# EIB_RHD32_HW01.net
KiCad netlist of a schematic drawn in EAGLE
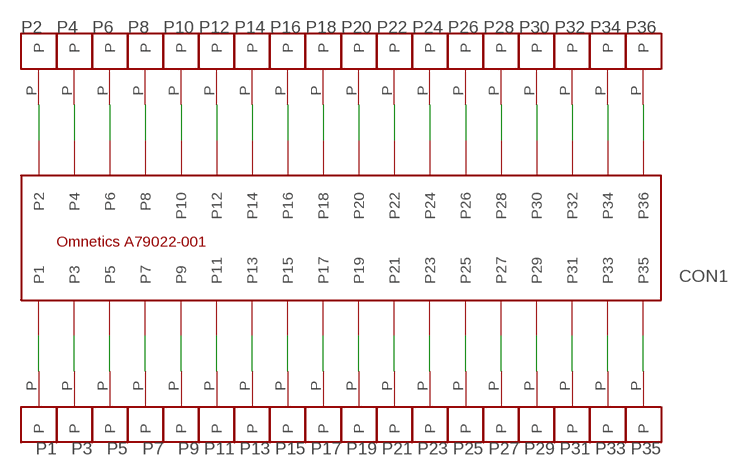
[diagram p0: schematic, sheet 1]

(export (version "E")
  (design (tool "Eeschema 10.0.6"))
  (components
    (comp (ref "CON1")
      (value "A79022-001_MALESMD")
      (footprint "eagle-import:A79026-001_MALE")
      (libsource (lib "eagle-import") (part "A79022-001_MALESMD"))
    )
    (comp (ref "P1")
      (value "EIB_SMALL_PIN")
      (footprint "eagle-import:EIB_SMALL_PIN")
      (libsource (lib "eagle-import") (part "EIB_SMALL_PIN"))
    )
    (comp (ref "P2")
      (value "EIB_SMALL_PIN")
      (footprint "eagle-import:EIB_SMALL_PIN")
      (libsource (lib "eagle-import") (part "EIB_SMALL_PIN"))
    )
    (comp (ref "P3")
      (value "EIB_SMALL_PIN")
      (footprint "eagle-import:EIB_SMALL_PIN")
      (libsource (lib "eagle-import") (part "EIB_SMALL_PIN"))
    )
    (comp (ref "P4")
      (value "EIB_SMALL_PIN")
      (footprint "eagle-import:EIB_SMALL_PIN")
      (libsource (lib "eagle-import") (part "EIB_SMALL_PIN"))
    )
    (comp (ref "P5")
      (value "EIB_SMALL_PIN")
      (footprint "eagle-import:EIB_SMALL_PIN")
      (libsource (lib "eagle-import") (part "EIB_SMALL_PIN"))
    )
    (comp (ref "P6")
      (value "EIB_SMALL_PIN")
      (footprint "eagle-import:EIB_SMALL_PIN")
      (libsource (lib "eagle-import") (part "EIB_SMALL_PIN"))
    )
    (comp (ref "P7")
      (value "EIB_SMALL_PIN")
      (footprint "eagle-import:EIB_SMALL_PIN")
      (libsource (lib "eagle-import") (part "EIB_SMALL_PIN"))
    )
    (comp (ref "P8")
      (value "EIB_SMALL_PIN")
      (footprint "eagle-import:EIB_SMALL_PIN")
      (libsource (lib "eagle-import") (part "EIB_SMALL_PIN"))
    )
    (comp (ref "P9")
      (value "EIB_SMALL_PIN")
      (footprint "eagle-import:EIB_SMALL_PIN")
      (libsource (lib "eagle-import") (part "EIB_SMALL_PIN"))
    )
    (comp (ref "P10")
      (value "EIB_SMALL_PIN")
      (footprint "eagle-import:EIB_SMALL_PIN")
      (libsource (lib "eagle-import") (part "EIB_SMALL_PIN"))
    )
    (comp (ref "P11")
      (value "EIB_SMALL_PIN")
      (footprint "eagle-import:EIB_SMALL_PIN")
      (libsource (lib "eagle-import") (part "EIB_SMALL_PIN"))
    )
    (comp (ref "P12")
      (value "EIB_SMALL_PIN")
      (footprint "eagle-import:EIB_SMALL_PIN")
      (libsource (lib "eagle-import") (part "EIB_SMALL_PIN"))
    )
    (comp (ref "P13")
      (value "EIB_SMALL_PIN")
      (footprint "eagle-import:EIB_SMALL_PIN")
      (libsource (lib "eagle-import") (part "EIB_SMALL_PIN"))
    )
    (comp (ref "P14")
      (value "EIB_SMALL_PIN")
      (footprint "eagle-import:EIB_SMALL_PIN")
      (libsource (lib "eagle-import") (part "EIB_SMALL_PIN"))
    )
    (comp (ref "P15")
      (value "EIB_SMALL_PIN")
      (footprint "eagle-import:EIB_SMALL_PIN")
      (libsource (lib "eagle-import") (part "EIB_SMALL_PIN"))
    )
    (comp (ref "P16")
      (value "EIB_SMALL_PIN")
      (footprint "eagle-import:EIB_SMALL_PIN")
      (libsource (lib "eagle-import") (part "EIB_SMALL_PIN"))
    )
    (comp (ref "P17")
      (value "EIB_SMALL_PIN")
      (footprint "eagle-import:EIB_SMALL_PIN")
      (libsource (lib "eagle-import") (part "EIB_SMALL_PIN"))
    )
    (comp (ref "P18")
      (value "EIB_SMALL_PIN")
      (footprint "eagle-import:EIB_SMALL_PIN")
      (libsource (lib "eagle-import") (part "EIB_SMALL_PIN"))
    )
    (comp (ref "P19")
      (value "EIB_SMALL_PIN")
      (footprint "eagle-import:EIB_SMALL_PIN")
      (libsource (lib "eagle-import") (part "EIB_SMALL_PIN"))
    )
    (comp (ref "P20")
      (value "EIB_SMALL_PIN")
      (footprint "eagle-import:EIB_SMALL_PIN")
      (libsource (lib "eagle-import") (part "EIB_SMALL_PIN"))
    )
    (comp (ref "P21")
      (value "EIB_SMALL_PIN")
      (footprint "eagle-import:EIB_SMALL_PIN")
      (libsource (lib "eagle-import") (part "EIB_SMALL_PIN"))
    )
    (comp (ref "P22")
      (value "EIB_SMALL_PIN")
      (footprint "eagle-import:EIB_SMALL_PIN")
      (libsource (lib "eagle-import") (part "EIB_SMALL_PIN"))
    )
    (comp (ref "P23")
      (value "EIB_SMALL_PIN")
      (footprint "eagle-import:EIB_SMALL_PIN")
      (libsource (lib "eagle-import") (part "EIB_SMALL_PIN"))
    )
    (comp (ref "P24")
      (value "EIB_SMALL_PIN")
      (footprint "eagle-import:EIB_SMALL_PIN")
      (libsource (lib "eagle-import") (part "EIB_SMALL_PIN"))
    )
    (comp (ref "P25")
      (value "EIB_SMALL_PIN")
      (footprint "eagle-import:EIB_SMALL_PIN")
      (libsource (lib "eagle-import") (part "EIB_SMALL_PIN"))
    )
    (comp (ref "P26")
      (value "EIB_SMALL_PIN")
      (footprint "eagle-import:EIB_SMALL_PIN")
      (libsource (lib "eagle-import") (part "EIB_SMALL_PIN"))
    )
    (comp (ref "P27")
      (value "EIB_SMALL_PIN")
      (footprint "eagle-import:EIB_SMALL_PIN")
      (libsource (lib "eagle-import") (part "EIB_SMALL_PIN"))
    )
    (comp (ref "P28")
      (value "EIB_SMALL_PIN")
      (footprint "eagle-import:EIB_SMALL_PIN")
      (libsource (lib "eagle-import") (part "EIB_SMALL_PIN"))
    )
    (comp (ref "P29")
      (value "EIB_SMALL_PIN")
      (footprint "eagle-import:EIB_SMALL_PIN")
      (libsource (lib "eagle-import") (part "EIB_SMALL_PIN"))
    )
    (comp (ref "P30")
      (value "EIB_SMALL_PIN")
      (footprint "eagle-import:EIB_SMALL_PIN")
      (libsource (lib "eagle-import") (part "EIB_SMALL_PIN"))
    )
    (comp (ref "P31")
      (value "EIB_SMALL_PIN")
      (footprint "eagle-import:EIB_SMALL_PIN")
      (libsource (lib "eagle-import") (part "EIB_SMALL_PIN"))
    )
    (comp (ref "P32")
      (value "EIB_SMALL_PIN")
      (footprint "eagle-import:EIB_SMALL_PIN")
      (libsource (lib "eagle-import") (part "EIB_SMALL_PIN"))
    )
    (comp (ref "P33")
      (value "EIB_SMALL_PIN")
      (footprint "eagle-import:EIB_SMALL_PIN")
      (libsource (lib "eagle-import") (part "EIB_SMALL_PIN"))
    )
    (comp (ref "P34")
      (value "EIB_SMALL_PIN")
      (footprint "eagle-import:EIB_SMALL_PIN")
      (libsource (lib "eagle-import") (part "EIB_SMALL_PIN"))
    )
    (comp (ref "P35")
      (value "EIB_SMALL_PIN")
      (footprint "eagle-import:EIB_SMALL_PIN")
      (libsource (lib "eagle-import") (part "EIB_SMALL_PIN"))
    )
    (comp (ref "P36")
      (value "EIB_SMALL_PIN")
      (footprint "eagle-import:EIB_SMALL_PIN")
      (libsource (lib "eagle-import") (part "EIB_SMALL_PIN"))
    )
  )
  (nets
    (net (code "1") (name "Net-(CON1-PadP1)") (class "Default")
      (node (ref "CON1") (pin "P1") (pinfunction "P1_P1") (pintype "bidirectional"))
      (node (ref "P1") (pin "P") (pinfunction "P_P") (pintype "bidirectional"))
    )
    (net (code "2") (name "Net-(CON1-PadP2)") (class "Default")
      (node (ref "CON1") (pin "P2") (pinfunction "P2_P2") (pintype "bidirectional"))
      (node (ref "P2") (pin "P") (pinfunction "P_P") (pintype "bidirectional"))
    )
    (net (code "3") (name "Net-(CON1-PadP3)") (class "Default")
      (node (ref "CON1") (pin "P3") (pinfunction "P3_P3") (pintype "bidirectional"))
      (node (ref "P3") (pin "P") (pinfunction "P_P") (pintype "bidirectional"))
    )
    (net (code "4") (name "Net-(CON1-PadP4)") (class "Default")
      (node (ref "CON1") (pin "P4") (pinfunction "P4_P4") (pintype "bidirectional"))
      (node (ref "P4") (pin "P") (pinfunction "P_P") (pintype "bidirectional"))
    )
    (net (code "5") (name "Net-(CON1-PadP5)") (class "Default")
      (node (ref "CON1") (pin "P5") (pinfunction "P5_P5") (pintype "bidirectional"))
      (node (ref "P5") (pin "P") (pinfunction "P_P") (pintype "bidirectional"))
    )
    (net (code "6") (name "Net-(CON1-PadP6)") (class "Default")
      (node (ref "CON1") (pin "P6") (pinfunction "P6_P6") (pintype "bidirectional"))
      (node (ref "P6") (pin "P") (pinfunction "P_P") (pintype "bidirectional"))
    )
    (net (code "7") (name "Net-(CON1-PadP7)") (class "Default")
      (node (ref "CON1") (pin "P7") (pinfunction "P7_P7") (pintype "bidirectional"))
      (node (ref "P7") (pin "P") (pinfunction "P_P") (pintype "bidirectional"))
    )
    (net (code "8") (name "Net-(CON1-PadP8)") (class "Default")
      (node (ref "CON1") (pin "P8") (pinfunction "P8_P8") (pintype "bidirectional"))
      (node (ref "P8") (pin "P") (pinfunction "P_P") (pintype "bidirectional"))
    )
    (net (code "9") (name "Net-(CON1-PadP9)") (class "Default")
      (node (ref "CON1") (pin "P9") (pinfunction "P9_P9") (pintype "bidirectional"))
      (node (ref "P9") (pin "P") (pinfunction "P_P") (pintype "bidirectional"))
    )
    (net (code "10") (name "Net-(CON1-PadP10)") (class "Default")
      (node (ref "CON1") (pin "P10") (pinfunction "P10_P10") (pintype "bidirectional"))
      (node (ref "P10") (pin "P") (pinfunction "P_P") (pintype "bidirectional"))
    )
    (net (code "11") (name "Net-(CON1-PadP11)") (class "Default")
      (node (ref "CON1") (pin "P11") (pinfunction "P11_P11") (pintype "bidirectional"))
      (node (ref "P11") (pin "P") (pinfunction "P_P") (pintype "bidirectional"))
    )
    (net (code "12") (name "Net-(CON1-PadP12)") (class "Default")
      (node (ref "CON1") (pin "P12") (pinfunction "P12_P12") (pintype "bidirectional"))
      (node (ref "P12") (pin "P") (pinfunction "P_P") (pintype "bidirectional"))
    )
    (net (code "13") (name "Net-(CON1-PadP13)") (class "Default")
      (node (ref "CON1") (pin "P13") (pinfunction "P13_P13") (pintype "bidirectional"))
      (node (ref "P13") (pin "P") (pinfunction "P_P") (pintype "bidirectional"))
    )
    (net (code "14") (name "Net-(CON1-PadP14)") (class "Default")
      (node (ref "CON1") (pin "P14") (pinfunction "P14_P14") (pintype "bidirectional"))
      (node (ref "P14") (pin "P") (pinfunction "P_P") (pintype "bidirectional"))
    )
    (net (code "15") (name "Net-(CON1-PadP15)") (class "Default")
      (node (ref "CON1") (pin "P15") (pinfunction "P15_P15") (pintype "bidirectional"))
      (node (ref "P15") (pin "P") (pinfunction "P_P") (pintype "bidirectional"))
    )
    (net (code "16") (name "Net-(CON1-PadP16)") (class "Default")
      (node (ref "CON1") (pin "P16") (pinfunction "P16_P16") (pintype "bidirectional"))
      (node (ref "P16") (pin "P") (pinfunction "P_P") (pintype "bidirectional"))
    )
    (net (code "17") (name "Net-(CON1-PadP17)") (class "Default")
      (node (ref "CON1") (pin "P17") (pinfunction "P17_P17") (pintype "bidirectional"))
      (node (ref "P17") (pin "P") (pinfunction "P_P") (pintype "bidirectional"))
    )
    (net (code "18") (name "Net-(CON1-PadP18)") (class "Default")
      (node (ref "CON1") (pin "P18") (pinfunction "P18_P18") (pintype "bidirectional"))
      (node (ref "P18") (pin "P") (pinfunction "P_P") (pintype "bidirectional"))
    )
    (net (code "19") (name "Net-(CON1-PadP19)") (class "Default")
      (node (ref "CON1") (pin "P19") (pinfunction "P19_P19") (pintype "bidirectional"))
      (node (ref "P19") (pin "P") (pinfunction "P_P") (pintype "bidirectional"))
    )
    (net (code "20") (name "Net-(CON1-PadP20)") (class "Default")
      (node (ref "CON1") (pin "P20") (pinfunction "P20_P20") (pintype "bidirectional"))
      (node (ref "P20") (pin "P") (pinfunction "P_P") (pintype "bidirectional"))
    )
    (net (code "21") (name "Net-(CON1-PadP21)") (class "Default")
      (node (ref "CON1") (pin "P21") (pinfunction "P21_P21") (pintype "bidirectional"))
      (node (ref "P21") (pin "P") (pinfunction "P_P") (pintype "bidirectional"))
    )
    (net (code "22") (name "Net-(CON1-PadP22)") (class "Default")
      (node (ref "CON1") (pin "P22") (pinfunction "P22_P22") (pintype "bidirectional"))
      (node (ref "P22") (pin "P") (pinfunction "P_P") (pintype "bidirectional"))
    )
    (net (code "23") (name "Net-(CON1-PadP23)") (class "Default")
      (node (ref "CON1") (pin "P23") (pinfunction "P23_P23") (pintype "bidirectional"))
      (node (ref "P23") (pin "P") (pinfunction "P_P") (pintype "bidirectional"))
    )
    (net (code "24") (name "Net-(CON1-PadP24)") (class "Default")
      (node (ref "CON1") (pin "P24") (pinfunction "P24_P24") (pintype "bidirectional"))
      (node (ref "P24") (pin "P") (pinfunction "P_P") (pintype "bidirectional"))
    )
    (net (code "25") (name "Net-(CON1-PadP25)") (class "Default")
      (node (ref "CON1") (pin "P25") (pinfunction "P25_P25") (pintype "bidirectional"))
      (node (ref "P25") (pin "P") (pinfunction "P_P") (pintype "bidirectional"))
    )
    (net (code "26") (name "Net-(CON1-PadP26)") (class "Default")
      (node (ref "CON1") (pin "P26") (pinfunction "P26_P26") (pintype "bidirectional"))
      (node (ref "P26") (pin "P") (pinfunction "P_P") (pintype "bidirectional"))
    )
    (net (code "27") (name "Net-(CON1-PadP27)") (class "Default")
      (node (ref "CON1") (pin "P27") (pinfunction "P27_P27") (pintype "bidirectional"))
      (node (ref "P27") (pin "P") (pinfunction "P_P") (pintype "bidirectional"))
    )
    (net (code "28") (name "Net-(CON1-PadP28)") (class "Default")
      (node (ref "CON1") (pin "P28") (pinfunction "P28_P28") (pintype "bidirectional"))
      (node (ref "P28") (pin "P") (pinfunction "P_P") (pintype "bidirectional"))
    )
    (net (code "29") (name "Net-(CON1-PadP29)") (class "Default")
      (node (ref "CON1") (pin "P29") (pinfunction "P29_P29") (pintype "bidirectional"))
      (node (ref "P29") (pin "P") (pinfunction "P_P") (pintype "bidirectional"))
    )
    (net (code "30") (name "Net-(CON1-PadP30)") (class "Default")
      (node (ref "CON1") (pin "P30") (pinfunction "P30_P30") (pintype "bidirectional"))
      (node (ref "P30") (pin "P") (pinfunction "P_P") (pintype "bidirectional"))
    )
    (net (code "31") (name "Net-(CON1-PadP31)") (class "Default")
      (node (ref "CON1") (pin "P31") (pinfunction "P31_P31") (pintype "bidirectional"))
      (node (ref "P31") (pin "P") (pinfunction "P_P") (pintype "bidirectional"))
    )
    (net (code "32") (name "Net-(CON1-PadP32)") (class "Default")
      (node (ref "CON1") (pin "P32") (pinfunction "P32_P32") (pintype "bidirectional"))
      (node (ref "P32") (pin "P") (pinfunction "P_P") (pintype "bidirectional"))
    )
    (net (code "33") (name "Net-(CON1-PadP33)") (class "Default")
      (node (ref "CON1") (pin "P33") (pinfunction "P33_P33") (pintype "bidirectional"))
      (node (ref "P33") (pin "P") (pinfunction "P_P") (pintype "bidirectional"))
    )
    (net (code "34") (name "Net-(CON1-PadP34)") (class "Default")
      (node (ref "CON1") (pin "P34") (pinfunction "P34_P34") (pintype "bidirectional"))
      (node (ref "P34") (pin "P") (pinfunction "P_P") (pintype "bidirectional"))
    )
    (net (code "35") (name "Net-(CON1-PadP35)") (class "Default")
      (node (ref "CON1") (pin "P35") (pinfunction "P35_P35") (pintype "bidirectional"))
      (node (ref "P35") (pin "P") (pinfunction "P_P") (pintype "bidirectional"))
    )
    (net (code "36") (name "Net-(CON1-PadP36)") (class "Default")
      (node (ref "CON1") (pin "P36") (pinfunction "P36_P36") (pintype "bidirectional"))
      (node (ref "P36") (pin "P") (pinfunction "P_P") (pintype "bidirectional"))
    )
  )
)
